# sensorboard.net
KiCad netlist of a schematic drawn in EAGLE
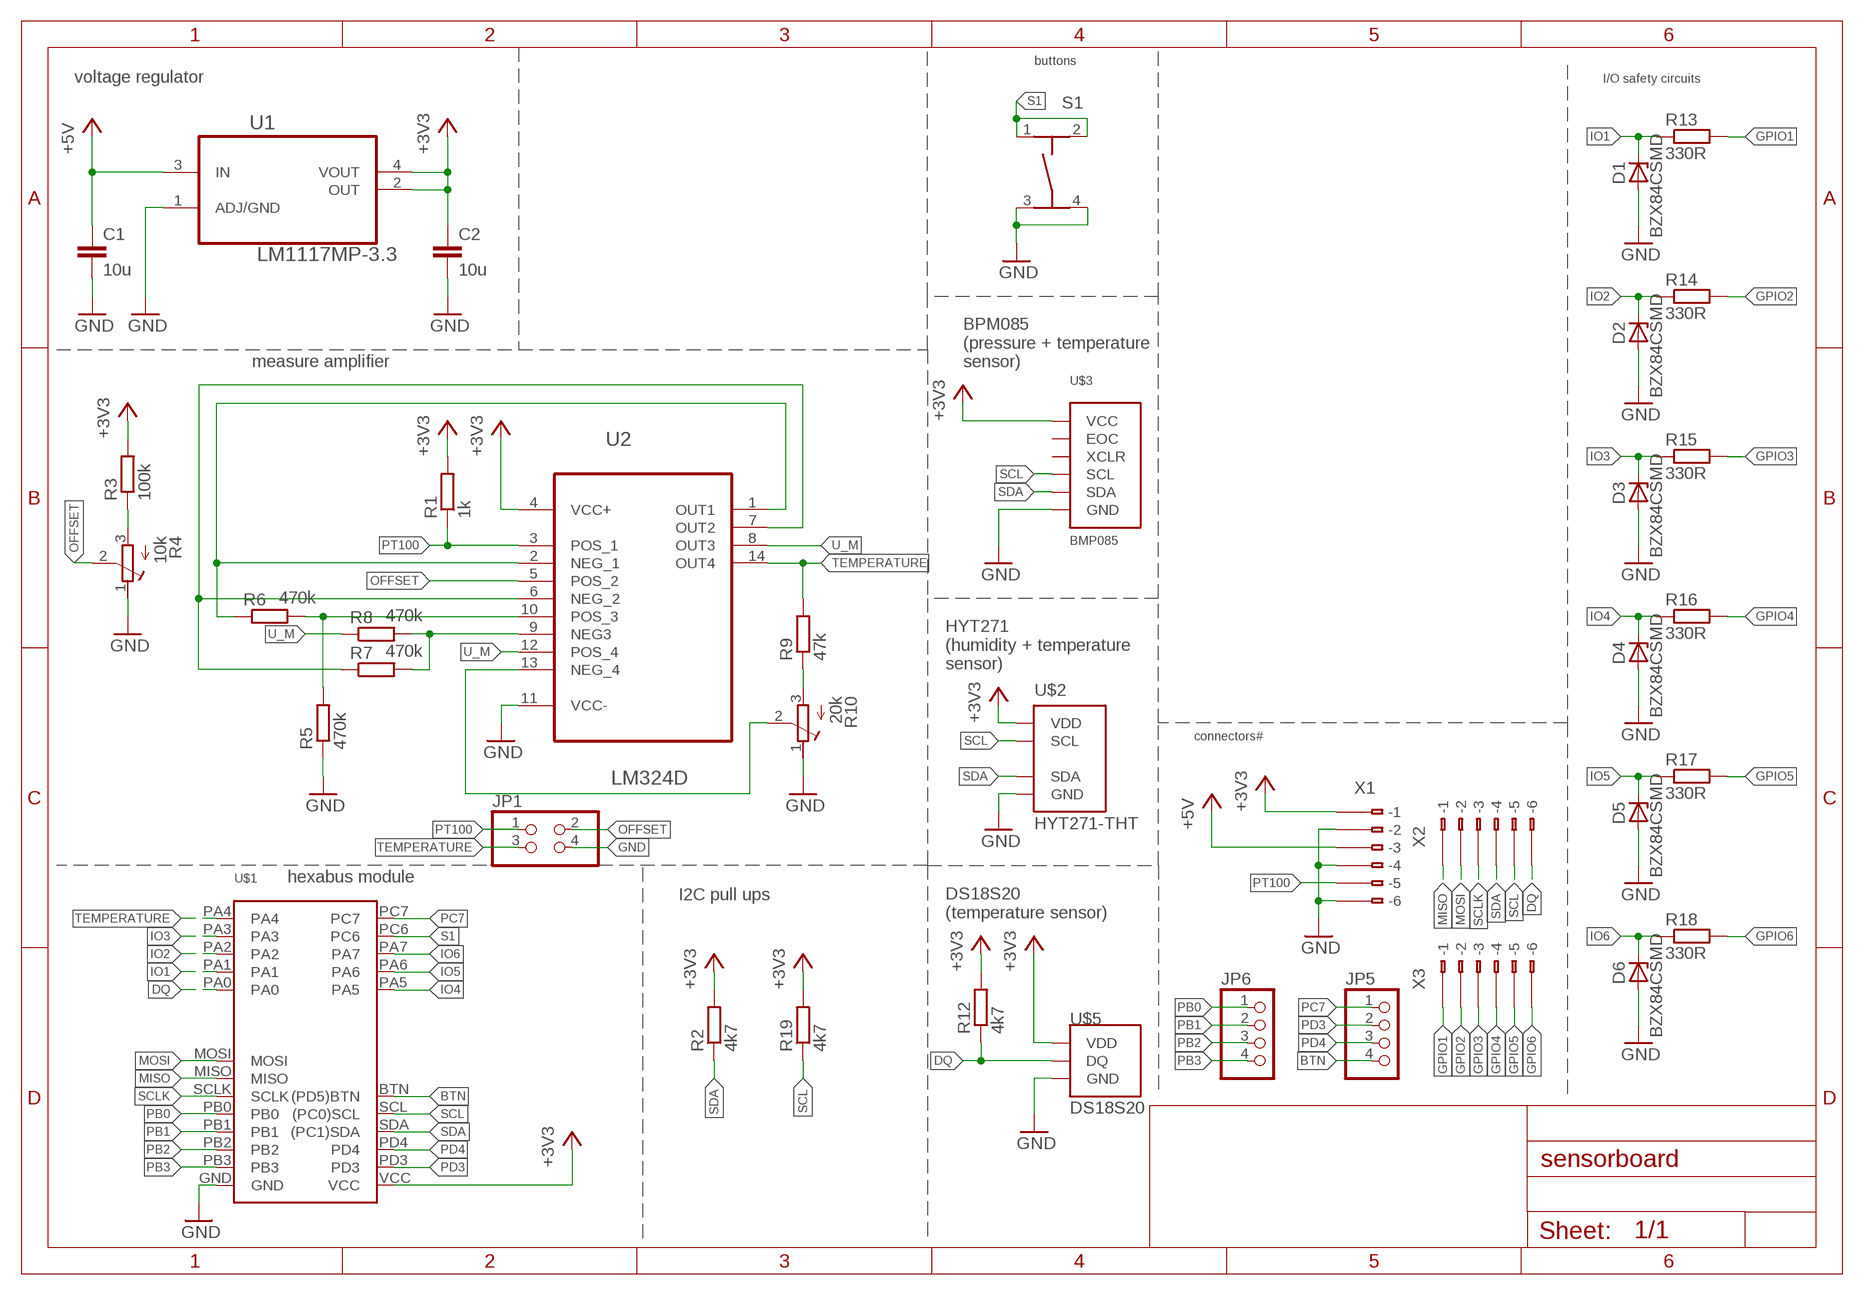
[diagram p0: schematic, sheet 1]

(export (version "E")
  (design (tool "Eeschema 10.0.6"))
  (components
    (comp (ref "C1")
      (value "10u")
      (footprint "eagle-import:C0805")
      (libsource (lib "eagle-import") (part "C-EUC0805"))
    )
    (comp (ref "C2")
      (value "10u")
      (footprint "eagle-import:C0805")
      (libsource (lib "eagle-import") (part "C-EUC0805"))
    )
    (comp (ref "D1")
      (value "BZX84CSMD")
      (footprint "eagle-import:TO236")
      (libsource (lib "eagle-import") (part "BZX84CSMD"))
    )
    (comp (ref "D2")
      (value "BZX84CSMD")
      (footprint "eagle-import:TO236")
      (libsource (lib "eagle-import") (part "BZX84CSMD"))
    )
    (comp (ref "D3")
      (value "BZX84CSMD")
      (footprint "eagle-import:TO236")
      (libsource (lib "eagle-import") (part "BZX84CSMD"))
    )
    (comp (ref "D4")
      (value "BZX84CSMD")
      (footprint "eagle-import:TO236")
      (libsource (lib "eagle-import") (part "BZX84CSMD"))
    )
    (comp (ref "D5")
      (value "BZX84CSMD")
      (footprint "eagle-import:TO236")
      (libsource (lib "eagle-import") (part "BZX84CSMD"))
    )
    (comp (ref "D6")
      (value "BZX84CSMD")
      (footprint "eagle-import:TO236")
      (libsource (lib "eagle-import") (part "BZX84CSMD"))
    )
    (comp (ref "JP1")
      (value "PINHD-2X2")
      (footprint "eagle-import:2X02")
      (libsource (lib "eagle-import") (part "PINHD-2X2"))
    )
    (comp (ref "JP5")
      (value "PINHD-1X4")
      (footprint "eagle-import:1X04")
      (libsource (lib "eagle-import") (part "PINHD-1X4"))
    )
    (comp (ref "JP6")
      (value "PINHD-1X4")
      (footprint "eagle-import:1X04")
      (libsource (lib "eagle-import") (part "PINHD-1X4"))
    )
    (comp (ref "R1")
      (value "1k")
      (footprint "eagle-import:R0805")
      (libsource (lib "eagle-import") (part "R-EU_R0805"))
    )
    (comp (ref "R2")
      (value "4k7")
      (footprint "eagle-import:R0805")
      (libsource (lib "eagle-import") (part "R-EU_R0805"))
    )
    (comp (ref "R3")
      (value "100k")
      (footprint "eagle-import:R0805")
      (libsource (lib "eagle-import") (part "R-EU_R0805"))
    )
    (comp (ref "R4")
      (value "10k")
      (footprint "eagle-import:RTRIMT93YB")
      (libsource (lib "eagle-import") (part "R-TRIMMT93YB"))
    )
    (comp (ref "R5")
      (value "470k")
      (footprint "eagle-import:R0805")
      (libsource (lib "eagle-import") (part "R-EU_R0805"))
    )
    (comp (ref "R6")
      (value "470k")
      (footprint "eagle-import:R0805")
      (libsource (lib "eagle-import") (part "R-EU_R0805"))
    )
    (comp (ref "R7")
      (value "470k")
      (footprint "eagle-import:R0805")
      (libsource (lib "eagle-import") (part "R-EU_R0805"))
    )
    (comp (ref "R8")
      (value "470k")
      (footprint "eagle-import:R0805")
      (libsource (lib "eagle-import") (part "R-EU_R0805"))
    )
    (comp (ref "R9")
      (value "47k")
      (footprint "eagle-import:R0805")
      (libsource (lib "eagle-import") (part "R-EU_R0805"))
    )
    (comp (ref "R10")
      (value "20k")
      (footprint "eagle-import:RTRIMT93YB")
      (libsource (lib "eagle-import") (part "R-TRIMMT93YB"))
    )
    (comp (ref "R12")
      (value "4k7")
      (footprint "eagle-import:R0805")
      (libsource (lib "eagle-import") (part "R-EU_R0805"))
    )
    (comp (ref "R13")
      (value "330R")
      (footprint "eagle-import:R0805")
      (libsource (lib "eagle-import") (part "R-EU_R0805"))
    )
    (comp (ref "R14")
      (value "330R")
      (footprint "eagle-import:R0805")
      (libsource (lib "eagle-import") (part "R-EU_R0805"))
    )
    (comp (ref "R15")
      (value "330R")
      (footprint "eagle-import:R0805")
      (libsource (lib "eagle-import") (part "R-EU_R0805"))
    )
    (comp (ref "R16")
      (value "330R")
      (footprint "eagle-import:R0805")
      (libsource (lib "eagle-import") (part "R-EU_R0805"))
    )
    (comp (ref "R17")
      (value "330R")
      (footprint "eagle-import:R0805")
      (libsource (lib "eagle-import") (part "R-EU_R0805"))
    )
    (comp (ref "R18")
      (value "330R")
      (footprint "eagle-import:R0805")
      (libsource (lib "eagle-import") (part "R-EU_R0805"))
    )
    (comp (ref "R19")
      (value "4k7")
      (footprint "eagle-import:R0805")
      (libsource (lib "eagle-import") (part "R-EU_R0805"))
    )
    (comp (ref "S1")
      (value "TASTER-9314_SMD")
      (footprint "eagle-import:TASTER-9314_SMD")
      (libsource (lib "eagle-import") (part "TASTER-9314_SMD"))
    )
    (comp (ref "U$1")
      (value "HEXABUS")
      (footprint "eagle-import:HEXABUS")
      (libsource (lib "eagle-import") (part "HEXABUS"))
    )
    (comp (ref "U$2")
      (value "HYT271-THT")
      (footprint "eagle-import:HYT271-THT")
      (libsource (lib "eagle-import") (part "HYT271-THT"))
    )
    (comp (ref "U$3")
      (value "BMP085")
      (footprint "eagle-import:BREAKOUT")
      (libsource (lib "eagle-import") (part "BMP085"))
    )
    (comp (ref "U$5")
      (value "DS18S20")
      (footprint "eagle-import:TO-92")
      (libsource (lib "eagle-import") (part "DS18S20"))
    )
    (comp (ref "U1")
      (value "LM1117MP-3.3")
      (footprint "eagle-import:SOT230P696X180-4N")
      (libsource (lib "eagle-import") (part "LM1117MP-3.3"))
    )
    (comp (ref "U2")
      (value "LM324D")
      (footprint "eagle-import:SOIC127P600X175-14N")
      (libsource (lib "eagle-import") (part "LM324D"))
    )
    (comp (ref "X1")
      (value "233-206")
      (footprint "eagle-import:233-206")
      (libsource (lib "eagle-import") (part "233-206"))
    )
    (comp (ref "X2")
      (value "233-206")
      (footprint "eagle-import:233-206")
      (libsource (lib "eagle-import") (part "233-206"))
    )
    (comp (ref "X3")
      (value "233-206")
      (footprint "eagle-import:233-206")
      (libsource (lib "eagle-import") (part "233-206"))
    )
  )
  (nets
    (net (code "1") (name "+3V3") (class "Default")
      (node (ref "C2") (pin "1") (pinfunction "1_1") (pintype "passive"))
      (node (ref "R1") (pin "2") (pinfunction "2_2") (pintype "passive"))
      (node (ref "R12") (pin "2") (pinfunction "2_2") (pintype "passive"))
      (node (ref "R19") (pin "2") (pinfunction "2_2") (pintype "passive"))
      (node (ref "R2") (pin "2") (pinfunction "2_2") (pintype "passive"))
      (node (ref "R3") (pin "2") (pinfunction "2_2") (pintype "passive"))
      (node (ref "U$1") (pin "VCC") (pinfunction "VCC_VCC") (pintype "bidirectional"))
      (node (ref "U$2") (pin "VDD") (pinfunction "VDD_VDD") (pintype "power_in"))
      (node (ref "U$3") (pin "VCC") (pinfunction "VCC_VCC") (pintype "bidirectional"))
      (node (ref "U$5") (pin "VDD") (pinfunction "VDD_VDD") (pintype "bidirectional"))
      (node (ref "U1") (pin "2") (pinfunction "OUT_2") (pintype "output"))
      (node (ref "U1") (pin "4") (pinfunction "VOUT_4") (pintype "output"))
      (node (ref "U2") (pin "4") (pinfunction "VCC+_4") (pintype "power_in"))
      (node (ref "X1") (pin "B1") (pinfunction "B-1_B1") (pintype "passive"))
    )
    (net (code "2") (name "+5V") (class "Default")
      (node (ref "C1") (pin "1") (pinfunction "1_1") (pintype "passive"))
      (node (ref "U1") (pin "3") (pinfunction "IN_3") (pintype "input"))
      (node (ref "X1") (pin "B3") (pinfunction "B-3_B3") (pintype "passive"))
    )
    (net (code "3") (name "BTN") (class "Default")
      (node (ref "JP5") (pin "4") (pinfunction "4_4") (pintype "passive"))
      (node (ref "U$1") (pin "BTN") (pinfunction "(PD5)BTN_BTN") (pintype "bidirectional"))
    )
    (net (code "4") (name "DQ") (class "Default")
      (node (ref "R12") (pin "1") (pinfunction "1_1") (pintype "passive"))
      (node (ref "U$1") (pin "PA0") (pinfunction "PA0_PA0") (pintype "bidirectional"))
      (node (ref "U$5") (pin "DQ") (pinfunction "DQ_DQ") (pintype "bidirectional"))
      (node (ref "X2") (pin "B6") (pinfunction "B-6_B6") (pintype "passive"))
    )
    (net (code "5") (name "GND") (class "Default")
      (node (ref "C1") (pin "2") (pinfunction "2_2") (pintype "passive"))
      (node (ref "C2") (pin "2") (pinfunction "2_2") (pintype "passive"))
      (node (ref "D1") (pin "A") (pinfunction "A_A") (pintype "passive"))
      (node (ref "D2") (pin "A") (pinfunction "A_A") (pintype "passive"))
      (node (ref "D3") (pin "A") (pinfunction "A_A") (pintype "passive"))
      (node (ref "D4") (pin "A") (pinfunction "A_A") (pintype "passive"))
      (node (ref "D5") (pin "A") (pinfunction "A_A") (pintype "passive"))
      (node (ref "D6") (pin "A") (pinfunction "A_A") (pintype "passive"))
      (node (ref "JP1") (pin "4") (pinfunction "4_4") (pintype "passive"))
      (node (ref "R10") (pin "1") (pinfunction "E_1") (pintype "passive"))
      (node (ref "R4") (pin "1") (pinfunction "E_1") (pintype "passive"))
      (node (ref "R5") (pin "1") (pinfunction "1_1") (pintype "passive"))
      (node (ref "S1") (pin "3") (pinfunction "3_3") (pintype "passive"))
      (node (ref "S1") (pin "4") (pinfunction "4_4") (pintype "passive"))
      (node (ref "U$1") (pin "GND") (pinfunction "GND_GND") (pintype "bidirectional"))
      (node (ref "U$2") (pin "GND") (pinfunction "GND_GND") (pintype "power_in"))
      (node (ref "U$3") (pin "GND") (pinfunction "GND_GND") (pintype "bidirectional"))
      (node (ref "U$5") (pin "GND") (pinfunction "GND_GND") (pintype "bidirectional"))
      (node (ref "U1") (pin "1") (pinfunction "ADJ/GND_1") (pintype "passive"))
      (node (ref "U2") (pin "11") (pinfunction "VCC-_11") (pintype "power_in"))
      (node (ref "X1") (pin "B2") (pinfunction "B-2_B2") (pintype "passive"))
      (node (ref "X1") (pin "B4") (pinfunction "B-4_B4") (pintype "passive"))
      (node (ref "X1") (pin "B6") (pinfunction "B-6_B6") (pintype "passive"))
    )
    (net (code "6") (name "GPIO1") (class "Default")
      (node (ref "R13") (pin "2") (pinfunction "2_2") (pintype "passive"))
      (node (ref "X3") (pin "B1") (pinfunction "B-1_B1") (pintype "passive"))
    )
    (net (code "7") (name "GPIO2") (class "Default")
      (node (ref "R14") (pin "2") (pinfunction "2_2") (pintype "passive"))
      (node (ref "X3") (pin "B2") (pinfunction "B-2_B2") (pintype "passive"))
    )
    (net (code "8") (name "GPIO3") (class "Default")
      (node (ref "R15") (pin "2") (pinfunction "2_2") (pintype "passive"))
      (node (ref "X3") (pin "B3") (pinfunction "B-3_B3") (pintype "passive"))
    )
    (net (code "9") (name "GPIO4") (class "Default")
      (node (ref "R16") (pin "2") (pinfunction "2_2") (pintype "passive"))
      (node (ref "X3") (pin "B4") (pinfunction "B-4_B4") (pintype "passive"))
    )
    (net (code "10") (name "GPIO5") (class "Default")
      (node (ref "R17") (pin "2") (pinfunction "2_2") (pintype "passive"))
      (node (ref "X3") (pin "B5") (pinfunction "B-5_B5") (pintype "passive"))
    )
    (net (code "11") (name "GPIO6") (class "Default")
      (node (ref "R18") (pin "2") (pinfunction "2_2") (pintype "passive"))
      (node (ref "X3") (pin "B6") (pinfunction "B-6_B6") (pintype "passive"))
    )
    (net (code "12") (name "IO1") (class "Default")
      (node (ref "D1") (pin "C") (pinfunction "C_C") (pintype "passive"))
      (node (ref "R13") (pin "1") (pinfunction "1_1") (pintype "passive"))
      (node (ref "U$1") (pin "PA1") (pinfunction "PA1_PA1") (pintype "bidirectional"))
    )
    (net (code "13") (name "IO2") (class "Default")
      (node (ref "D2") (pin "C") (pinfunction "C_C") (pintype "passive"))
      (node (ref "R14") (pin "1") (pinfunction "1_1") (pintype "passive"))
      (node (ref "U$1") (pin "PA2") (pinfunction "PA2_PA2") (pintype "bidirectional"))
    )
    (net (code "14") (name "IO3") (class "Default")
      (node (ref "D3") (pin "C") (pinfunction "C_C") (pintype "passive"))
      (node (ref "R15") (pin "1") (pinfunction "1_1") (pintype "passive"))
      (node (ref "U$1") (pin "PA3") (pinfunction "PA3_PA3") (pintype "bidirectional"))
    )
    (net (code "15") (name "IO4") (class "Default")
      (node (ref "D4") (pin "C") (pinfunction "C_C") (pintype "passive"))
      (node (ref "R16") (pin "1") (pinfunction "1_1") (pintype "passive"))
      (node (ref "U$1") (pin "PA5") (pinfunction "PA5_PA5") (pintype "bidirectional"))
    )
    (net (code "16") (name "IO5") (class "Default")
      (node (ref "D5") (pin "C") (pinfunction "C_C") (pintype "passive"))
      (node (ref "R17") (pin "1") (pinfunction "1_1") (pintype "passive"))
      (node (ref "U$1") (pin "PA6") (pinfunction "PA6_PA6") (pintype "bidirectional"))
    )
    (net (code "17") (name "IO6") (class "Default")
      (node (ref "D6") (pin "C") (pinfunction "C_C") (pintype "passive"))
      (node (ref "R18") (pin "1") (pinfunction "1_1") (pintype "passive"))
      (node (ref "U$1") (pin "PA7") (pinfunction "PA7_PA7") (pintype "bidirectional"))
    )
    (net (code "18") (name "MISO") (class "Default")
      (node (ref "U$1") (pin "MISO") (pinfunction "MISO_MISO") (pintype "bidirectional"))
      (node (ref "X2") (pin "B1") (pinfunction "B-1_B1") (pintype "passive"))
    )
    (net (code "19") (name "MOSI") (class "Default")
      (node (ref "U$1") (pin "MOSI") (pinfunction "MOSI_MOSI") (pintype "bidirectional"))
      (node (ref "X2") (pin "B2") (pinfunction "B-2_B2") (pintype "passive"))
    )
    (net (code "20") (name "Net-(R4-A)") (class "Default")
      (node (ref "R3") (pin "1") (pinfunction "1_1") (pintype "passive"))
      (node (ref "R4") (pin "3") (pinfunction "A_3") (pintype "passive"))
    )
    (net (code "21") (name "Net-(R10-A)") (class "Default")
      (node (ref "R10") (pin "3") (pinfunction "A_3") (pintype "passive"))
      (node (ref "R9") (pin "1") (pinfunction "1_1") (pintype "passive"))
    )
    (net (code "22") (name "Net-(R10-S)") (class "Default")
      (node (ref "R10") (pin "2") (pinfunction "S_2") (pintype "passive"))
      (node (ref "U2") (pin "13") (pinfunction "NEG_4_13") (pintype "input"))
    )
    (net (code "23") (name "Net-(U2-NEG3)") (class "Default")
      (node (ref "R7") (pin "2") (pinfunction "2_2") (pintype "passive"))
      (node (ref "R8") (pin "2") (pinfunction "2_2") (pintype "passive"))
      (node (ref "U2") (pin "9") (pinfunction "NEG3_9") (pintype "input"))
    )
    (net (code "24") (name "Net-(U2-NEG_1)") (class "Default")
      (node (ref "R6") (pin "1") (pinfunction "1_1") (pintype "passive"))
      (node (ref "U2") (pin "1") (pinfunction "OUT1_1") (pintype "output"))
      (node (ref "U2") (pin "2") (pinfunction "NEG_1_2") (pintype "input"))
    )
    (net (code "25") (name "Net-(U2-NEG_2)") (class "Default")
      (node (ref "R7") (pin "1") (pinfunction "1_1") (pintype "passive"))
      (node (ref "U2") (pin "6") (pinfunction "NEG_2_6") (pintype "input"))
      (node (ref "U2") (pin "7") (pinfunction "OUT2_7") (pintype "output"))
    )
    (net (code "26") (name "Net-(U2-POS_3)") (class "Default")
      (node (ref "R5") (pin "2") (pinfunction "2_2") (pintype "passive"))
      (node (ref "R6") (pin "2") (pinfunction "2_2") (pintype "passive"))
      (node (ref "U2") (pin "10") (pinfunction "POS_3_10") (pintype "input"))
    )
    (net (code "27") (name "OFFSET") (class "Default")
      (node (ref "JP1") (pin "2") (pinfunction "2_2") (pintype "passive"))
      (node (ref "R4") (pin "2") (pinfunction "S_2") (pintype "passive"))
      (node (ref "U2") (pin "5") (pinfunction "POS_2_5") (pintype "input"))
    )
    (net (code "28") (name "PB0") (class "Default")
      (node (ref "JP6") (pin "1") (pinfunction "1_1") (pintype "passive"))
      (node (ref "U$1") (pin "PB0") (pinfunction "PB0_PB0") (pintype "bidirectional"))
    )
    (net (code "29") (name "PB1") (class "Default")
      (node (ref "JP6") (pin "2") (pinfunction "2_2") (pintype "passive"))
      (node (ref "U$1") (pin "PB1") (pinfunction "PB1_PB1") (pintype "bidirectional"))
    )
    (net (code "30") (name "PB2") (class "Default")
      (node (ref "JP6") (pin "3") (pinfunction "3_3") (pintype "passive"))
      (node (ref "U$1") (pin "PB2") (pinfunction "PB2_PB2") (pintype "bidirectional"))
    )
    (net (code "31") (name "PB3") (class "Default")
      (node (ref "JP6") (pin "4") (pinfunction "4_4") (pintype "passive"))
      (node (ref "U$1") (pin "PB3") (pinfunction "PB3_PB3") (pintype "bidirectional"))
    )
    (net (code "32") (name "PC7") (class "Default")
      (node (ref "JP5") (pin "1") (pinfunction "1_1") (pintype "passive"))
      (node (ref "U$1") (pin "PC7") (pinfunction "PC7_PC7") (pintype "bidirectional"))
    )
    (net (code "33") (name "PD3") (class "Default")
      (node (ref "JP5") (pin "2") (pinfunction "2_2") (pintype "passive"))
      (node (ref "U$1") (pin "PD3") (pinfunction "PD3_PD3") (pintype "bidirectional"))
    )
    (net (code "34") (name "PD4") (class "Default")
      (node (ref "JP5") (pin "3") (pinfunction "3_3") (pintype "passive"))
      (node (ref "U$1") (pin "PD4") (pinfunction "PD4_PD4") (pintype "bidirectional"))
    )
    (net (code "35") (name "PT100") (class "Default")
      (node (ref "JP1") (pin "1") (pinfunction "1_1") (pintype "passive"))
      (node (ref "R1") (pin "1") (pinfunction "1_1") (pintype "passive"))
      (node (ref "U2") (pin "3") (pinfunction "POS_1_3") (pintype "input"))
      (node (ref "X1") (pin "B5") (pinfunction "B-5_B5") (pintype "passive"))
    )
    (net (code "36") (name "S1") (class "Default")
      (node (ref "S1") (pin "1") (pinfunction "1_1") (pintype "passive"))
      (node (ref "S1") (pin "2") (pinfunction "2_2") (pintype "passive"))
      (node (ref "U$1") (pin "PC6") (pinfunction "PC6_PC6") (pintype "bidirectional"))
    )
    (net (code "37") (name "SCL") (class "Default")
      (node (ref "R19") (pin "1") (pinfunction "1_1") (pintype "passive"))
      (node (ref "U$1") (pin "SCL") (pinfunction "(PC0)SCL_SCL") (pintype "bidirectional"))
      (node (ref "U$2") (pin "SCL") (pinfunction "SCL_SCL") (pintype "bidirectional"))
      (node (ref "U$3") (pin "SCL") (pinfunction "SCL_SCL") (pintype "bidirectional"))
      (node (ref "X2") (pin "B5") (pinfunction "B-5_B5") (pintype "passive"))
    )
    (net (code "38") (name "SCLK") (class "Default")
      (node (ref "U$1") (pin "SCLK") (pinfunction "SCLK_SCLK") (pintype "bidirectional"))
      (node (ref "X2") (pin "B3") (pinfunction "B-3_B3") (pintype "passive"))
    )
    (net (code "39") (name "SDA") (class "Default")
      (node (ref "R2") (pin "1") (pinfunction "1_1") (pintype "passive"))
      (node (ref "U$1") (pin "SDA") (pinfunction "(PC1)SDA_SDA") (pintype "bidirectional"))
      (node (ref "U$2") (pin "SDA") (pinfunction "SDA_SDA") (pintype "bidirectional"))
      (node (ref "U$3") (pin "SDA") (pinfunction "SDA_SDA") (pintype "bidirectional"))
      (node (ref "X2") (pin "B4") (pinfunction "B-4_B4") (pintype "passive"))
    )
    (net (code "40") (name "TEMPERATURE") (class "Default")
      (node (ref "JP1") (pin "3") (pinfunction "3_3") (pintype "passive"))
      (node (ref "R9") (pin "2") (pinfunction "2_2") (pintype "passive"))
      (node (ref "U$1") (pin "PA4") (pinfunction "PA4_PA4") (pintype "bidirectional"))
      (node (ref "U2") (pin "14") (pinfunction "OUT4_14") (pintype "output"))
    )
    (net (code "41") (name "U_M") (class "Default")
      (node (ref "R8") (pin "1") (pinfunction "1_1") (pintype "passive"))
      (node (ref "U2") (pin "12") (pinfunction "POS_4_12") (pintype "input"))
      (node (ref "U2") (pin "8") (pinfunction "OUT3_8") (pintype "output"))
    )
    (net (code "42") (name "unconnected-(U$3-PadEOC)") (class "Default")
      (node (ref "U$3") (pin "EOC") (pinfunction "EOC_EOC") (pintype "bidirectional"))
    )
    (net (code "43") (name "unconnected-(U$3-PadXCLR)") (class "Default")
      (node (ref "U$3") (pin "XCLR") (pinfunction "XCLR_XCLR") (pintype "bidirectional"))
    )
    (net (code "44") (name "unconnected-(X1--1-PadA1)") (class "Default")
      (node (ref "X1") (pin "A1") (pinfunction "-1_A1") (pintype "passive"))
    )
    (net (code "45") (name "unconnected-(X1--2-PadA2)") (class "Default")
      (node (ref "X1") (pin "A2") (pinfunction "-2_A2") (pintype "passive"))
    )
    (net (code "46") (name "unconnected-(X1--3-PadA3)") (class "Default")
      (node (ref "X1") (pin "A3") (pinfunction "-3_A3") (pintype "passive"))
    )
    (net (code "47") (name "unconnected-(X1--4-PadA4)") (class "Default")
      (node (ref "X1") (pin "A4") (pinfunction "-4_A4") (pintype "passive"))
    )
    (net (code "48") (name "unconnected-(X1--5-PadA5)") (class "Default")
      (node (ref "X1") (pin "A5") (pinfunction "-5_A5") (pintype "passive"))
    )
    (net (code "49") (name "unconnected-(X1--6-PadA6)") (class "Default")
      (node (ref "X1") (pin "A6") (pinfunction "-6_A6") (pintype "passive"))
    )
    (net (code "50") (name "unconnected-(X2--1-PadA1)") (class "Default")
      (node (ref "X2") (pin "A1") (pinfunction "-1_A1") (pintype "passive"))
    )
    (net (code "51") (name "unconnected-(X2--2-PadA2)") (class "Default")
      (node (ref "X2") (pin "A2") (pinfunction "-2_A2") (pintype "passive"))
    )
    (net (code "52") (name "unconnected-(X2--3-PadA3)") (class "Default")
      (node (ref "X2") (pin "A3") (pinfunction "-3_A3") (pintype "passive"))
    )
    (net (code "53") (name "unconnected-(X2--4-PadA4)") (class "Default")
      (node (ref "X2") (pin "A4") (pinfunction "-4_A4") (pintype "passive"))
    )
    (net (code "54") (name "unconnected-(X2--5-PadA5)") (class "Default")
      (node (ref "X2") (pin "A5") (pinfunction "-5_A5") (pintype "passive"))
    )
    (net (code "55") (name "unconnected-(X2--6-PadA6)") (class "Default")
      (node (ref "X2") (pin "A6") (pinfunction "-6_A6") (pintype "passive"))
    )
    (net (code "56") (name "unconnected-(X3--1-PadA1)") (class "Default")
      (node (ref "X3") (pin "A1") (pinfunction "-1_A1") (pintype "passive"))
    )
    (net (code "57") (name "unconnected-(X3--2-PadA2)") (class "Default")
      (node (ref "X3") (pin "A2") (pinfunction "-2_A2") (pintype "passive"))
    )
    (net (code "58") (name "unconnected-(X3--3-PadA3)") (class "Default")
      (node (ref "X3") (pin "A3") (pinfunction "-3_A3") (pintype "passive"))
    )
    (net (code "59") (name "unconnected-(X3--4-PadA4)") (class "Default")
      (node (ref "X3") (pin "A4") (pinfunction "-4_A4") (pintype "passive"))
    )
    (net (code "60") (name "unconnected-(X3--5-PadA5)") (class "Default")
      (node (ref "X3") (pin "A5") (pinfunction "-5_A5") (pintype "passive"))
    )
    (net (code "61") (name "unconnected-(X3--6-PadA6)") (class "Default")
      (node (ref "X3") (pin "A6") (pinfunction "-6_A6") (pintype "passive"))
    )
  )
)
